# WiFi-Bee_v10.net
KiCad netlist of a schematic drawn in EAGLE
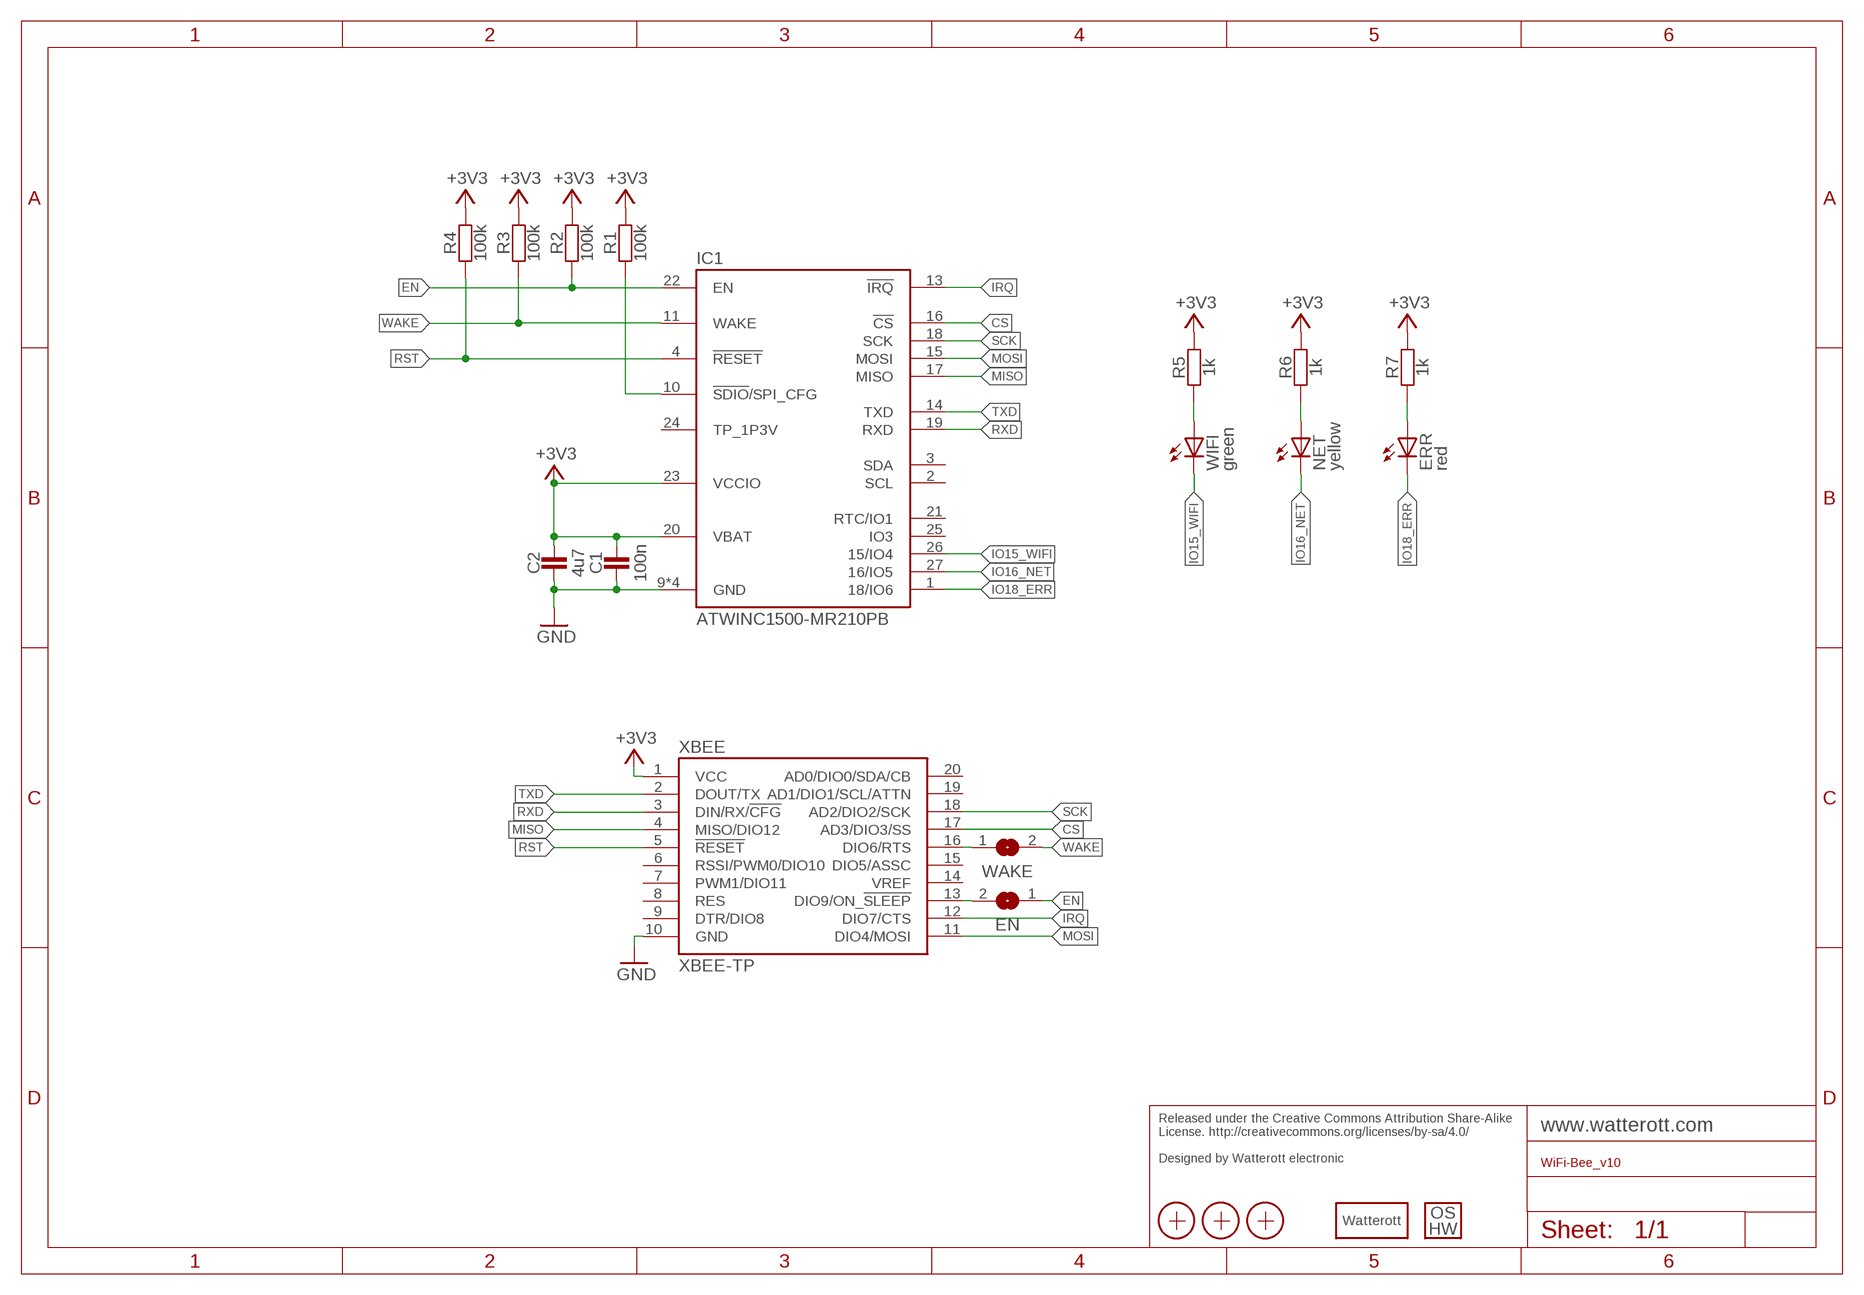
[diagram p0: schematic, sheet 1]

(export (version "E")
  (design (tool "Eeschema 10.0.6"))
  (components
    (comp (ref "C1")
      (value "100n")
      (footprint "eagle-import:C0402")
      (libsource (lib "eagle-import") (part "CAPACITOR-0402"))
    )
    (comp (ref "C2")
      (value "4u7")
      (footprint "eagle-import:C0402")
      (libsource (lib "eagle-import") (part "CAPACITOR-0402"))
    )
    (comp (ref "EN")
      (value "JUMPER2-0402")
      (footprint "eagle-import:JUMPER2-0402")
      (libsource (lib "eagle-import") (part "JUMPER2-0402"))
    )
    (comp (ref "ERR")
      (value "red")
      (footprint "eagle-import:C0603")
      (libsource (lib "eagle-import") (part "LED-0603"))
    )
    (comp (ref "IC1")
      (value "ATWINC1500-MR210PB")
      (footprint "eagle-import:ATWINC1500-MX210")
      (libsource (lib "eagle-import") (part "ATWINC1500-MR210PB"))
    )
    (comp (ref "LOGO3")
      (value "LOGO_SPARK-2")
      (footprint "eagle-import:SPARK_2MM")
      (libsource (lib "eagle-import") (part "LOGO_SPARK-2"))
    )
    (comp (ref "LOGO4")
      (value "LOGO_OSHW-2")
      (footprint "eagle-import:OSHW_2MM")
      (libsource (lib "eagle-import") (part "LOGO_OSHW-2"))
    )
    (comp (ref "NET")
      (value "yellow")
      (footprint "eagle-import:C0603")
      (libsource (lib "eagle-import") (part "LED-0603"))
    )
    (comp (ref "R1")
      (value "100k")
      (footprint "eagle-import:C0402")
      (libsource (lib "eagle-import") (part "RESISTOR-0402"))
    )
    (comp (ref "R2")
      (value "100k")
      (footprint "eagle-import:C0402")
      (libsource (lib "eagle-import") (part "RESISTOR-0402"))
    )
    (comp (ref "R3")
      (value "100k")
      (footprint "eagle-import:C0402")
      (libsource (lib "eagle-import") (part "RESISTOR-0402"))
    )
    (comp (ref "R4")
      (value "100k")
      (footprint "eagle-import:C0402")
      (libsource (lib "eagle-import") (part "RESISTOR-0402"))
    )
    (comp (ref "R5")
      (value "1k")
      (footprint "eagle-import:C0402")
      (libsource (lib "eagle-import") (part "RESISTOR-0402"))
    )
    (comp (ref "R6")
      (value "1k")
      (footprint "eagle-import:C0402")
      (libsource (lib "eagle-import") (part "RESISTOR-0402"))
    )
    (comp (ref "R7")
      (value "1k")
      (footprint "eagle-import:C0402")
      (libsource (lib "eagle-import") (part "RESISTOR-0402"))
    )
    (comp (ref "WAKE")
      (value "JUMPER2-0402")
      (footprint "eagle-import:JUMPER2-0402")
      (libsource (lib "eagle-import") (part "JUMPER2-0402"))
    )
    (comp (ref "WIFI")
      (value "green")
      (footprint "eagle-import:C0603")
      (libsource (lib "eagle-import") (part "LED-0603"))
    )
    (comp (ref "X1")
      (value "PASSER-07")
      (footprint "eagle-import:PASSER_07MM")
      (libsource (lib "eagle-import") (part "PASSER-07"))
    )
    (comp (ref "X2")
      (value "PASSER-07")
      (footprint "eagle-import:PASSER_07MM")
      (libsource (lib "eagle-import") (part "PASSER-07"))
    )
    (comp (ref "X3")
      (value "PASSER-07")
      (footprint "eagle-import:PASSER_07MM")
      (libsource (lib "eagle-import") (part "PASSER-07"))
    )
    (comp (ref "XBEE")
      (value "XBEE-TP")
      (footprint "eagle-import:XBEE_TP")
      (libsource (lib "eagle-import") (part "XBEE-TP"))
    )
  )
  (nets
    (net (code "1") (name "+3V3") (class "Default")
      (node (ref "C1") (pin "2") (pinfunction "2_2") (pintype "passive"))
      (node (ref "C2") (pin "2") (pinfunction "2_2") (pintype "passive"))
      (node (ref "IC1") (pin "20") (pinfunction "VBAT_20") (pintype "power_in"))
      (node (ref "IC1") (pin "23") (pinfunction "VCCIO_23") (pintype "power_in"))
      (node (ref "R1") (pin "2") (pinfunction "2_2") (pintype "passive"))
      (node (ref "R2") (pin "2") (pinfunction "2_2") (pintype "passive"))
      (node (ref "R3") (pin "2") (pinfunction "2_2") (pintype "passive"))
      (node (ref "R4") (pin "2") (pinfunction "2_2") (pintype "passive"))
      (node (ref "R5") (pin "2") (pinfunction "2_2") (pintype "passive"))
      (node (ref "R6") (pin "2") (pinfunction "2_2") (pintype "passive"))
      (node (ref "R7") (pin "2") (pinfunction "2_2") (pintype "passive"))
      (node (ref "XBEE") (pin "1") (pinfunction "VCC_1") (pintype "power_in"))
    )
    (net (code "2") (name "CS") (class "Default")
      (node (ref "IC1") (pin "16") (pinfunction "~{CS}_16") (pintype "input"))
      (node (ref "XBEE") (pin "17") (pinfunction "AD3/DIO3/SS_17") (pintype "bidirectional"))
    )
    (net (code "3") (name "EN") (class "Default")
      (node (ref "EN") (pin "1") (pinfunction "1_1") (pintype "passive"))
      (node (ref "IC1") (pin "22") (pinfunction "EN_22") (pintype "input"))
      (node (ref "R2") (pin "1") (pinfunction "1_1") (pintype "passive"))
    )
    (net (code "4") (name "GND") (class "Default")
      (node (ref "C1") (pin "1") (pinfunction "1_1") (pintype "passive"))
      (node (ref "C2") (pin "1") (pinfunction "1_1") (pintype "passive"))
      (node (ref "IC1") (pin "12") (pinfunction "GND_12") (pintype "power_in"))
      (node (ref "IC1") (pin "28") (pinfunction "GND_28") (pintype "power_in"))
      (node (ref "IC1") (pin "9") (pinfunction "GND_9") (pintype "power_in"))
      (node (ref "IC1") (pin "GND") (pinfunction "GND_GND") (pintype "power_in"))
      (node (ref "XBEE") (pin "10") (pinfunction "GND_10") (pintype "power_in"))
    )
    (net (code "5") (name "IO15_WIFI") (class "Default")
      (node (ref "IC1") (pin "26") (pinfunction "15/IO4_26") (pintype "bidirectional"))
      (node (ref "WIFI") (pin "C") (pinfunction "C_C") (pintype "passive"))
    )
    (net (code "6") (name "IO16_NET") (class "Default")
      (node (ref "IC1") (pin "27") (pinfunction "16/IO5_27") (pintype "bidirectional"))
      (node (ref "NET") (pin "C") (pinfunction "C_C") (pintype "passive"))
    )
    (net (code "7") (name "IO18_ERR") (class "Default")
      (node (ref "ERR") (pin "C") (pinfunction "C_C") (pintype "passive"))
      (node (ref "IC1") (pin "1") (pinfunction "18/IO6_1") (pintype "bidirectional"))
    )
    (net (code "8") (name "IRQ") (class "Default")
      (node (ref "IC1") (pin "13") (pinfunction "~{IRQ}_13") (pintype "output"))
      (node (ref "XBEE") (pin "12") (pinfunction "DIO7/CTS_12") (pintype "bidirectional"))
    )
    (net (code "9") (name "MISO") (class "Default")
      (node (ref "IC1") (pin "17") (pinfunction "MISO_17") (pintype "output"))
      (node (ref "XBEE") (pin "4") (pinfunction "MISO/DIO12_4") (pintype "bidirectional"))
    )
    (net (code "10") (name "MOSI") (class "Default")
      (node (ref "IC1") (pin "15") (pinfunction "MOSI_15") (pintype "input"))
      (node (ref "XBEE") (pin "11") (pinfunction "DIO4/MOSI_11") (pintype "bidirectional"))
    )
    (net (code "11") (name "Net-(ERR-PadA)") (class "Default")
      (node (ref "ERR") (pin "A") (pinfunction "A_A") (pintype "passive"))
      (node (ref "R7") (pin "1") (pinfunction "1_1") (pintype "passive"))
    )
    (net (code "12") (name "Net-(IC1-~{SDIO}{slash}SPI_CFG)") (class "Default")
      (node (ref "IC1") (pin "10") (pinfunction "~{SDIO}/SPI_CFG_10") (pintype "input"))
      (node (ref "R1") (pin "1") (pinfunction "1_1") (pintype "passive"))
    )
    (net (code "13") (name "Net-(NET-PadA)") (class "Default")
      (node (ref "NET") (pin "A") (pinfunction "A_A") (pintype "passive"))
      (node (ref "R6") (pin "1") (pinfunction "1_1") (pintype "passive"))
    )
    (net (code "14") (name "Net-(R5-Pad1)") (class "Default")
      (node (ref "R5") (pin "1") (pinfunction "1_1") (pintype "passive"))
      (node (ref "WIFI") (pin "A") (pinfunction "A_A") (pintype "passive"))
    )
    (net (code "15") (name "Net-(XBEE-DIO6{slash}RTS)") (class "Default")
      (node (ref "WAKE") (pin "1") (pinfunction "1_1") (pintype "passive"))
      (node (ref "XBEE") (pin "16") (pinfunction "DIO6/RTS_16") (pintype "bidirectional"))
    )
    (net (code "16") (name "Net-(XBEE-DIO9{slash}ON_~{SLEEP})") (class "Default")
      (node (ref "EN") (pin "2") (pinfunction "2_2") (pintype "passive"))
      (node (ref "XBEE") (pin "13") (pinfunction "DIO9/ON_~{SLEEP}_13") (pintype "bidirectional"))
    )
    (net (code "17") (name "RST") (class "Default")
      (node (ref "IC1") (pin "4") (pinfunction "~{RESET}_4") (pintype "input"))
      (node (ref "R4") (pin "1") (pinfunction "1_1") (pintype "passive"))
      (node (ref "XBEE") (pin "5") (pinfunction "~{RESET}_5") (pintype "bidirectional"))
    )
    (net (code "18") (name "RXD") (class "Default")
      (node (ref "IC1") (pin "19") (pinfunction "RXD_19") (pintype "input"))
      (node (ref "XBEE") (pin "3") (pinfunction "DIN/RX/~{CFG}_3") (pintype "bidirectional"))
    )
    (net (code "19") (name "SCK") (class "Default")
      (node (ref "IC1") (pin "18") (pinfunction "SCK_18") (pintype "input"))
      (node (ref "XBEE") (pin "18") (pinfunction "AD2/DIO2/SCK_18") (pintype "bidirectional"))
    )
    (net (code "20") (name "TXD") (class "Default")
      (node (ref "IC1") (pin "14") (pinfunction "TXD_14") (pintype "output"))
      (node (ref "XBEE") (pin "2") (pinfunction "DOUT/TX_2") (pintype "bidirectional"))
    )
    (net (code "21") (name "WAKE") (class "Default")
      (node (ref "IC1") (pin "11") (pinfunction "WAKE_11") (pintype "input"))
      (node (ref "R3") (pin "1") (pinfunction "1_1") (pintype "passive"))
      (node (ref "WAKE") (pin "2") (pinfunction "2_2") (pintype "passive"))
    )
    (net (code "22") (name "unconnected-(IC1-IO3-Pad25)") (class "Default")
      (node (ref "IC1") (pin "25") (pinfunction "IO3_25") (pintype "bidirectional"))
    )
    (net (code "23") (name "unconnected-(IC1-RTC{slash}IO1-Pad21)") (class "Default")
      (node (ref "IC1") (pin "21") (pinfunction "RTC/IO1_21") (pintype "bidirectional"))
    )
    (net (code "24") (name "unconnected-(IC1-SCL-Pad2)") (class "Default")
      (node (ref "IC1") (pin "2") (pinfunction "SCL_2") (pintype "bidirectional"))
    )
    (net (code "25") (name "unconnected-(IC1-SDA-Pad3)") (class "Default")
      (node (ref "IC1") (pin "3") (pinfunction "SDA_3") (pintype "bidirectional"))
    )
    (net (code "26") (name "unconnected-(IC1-TP_1P3V-Pad24)") (class "Default")
      (node (ref "IC1") (pin "24") (pinfunction "TP_1P3V_24") (pintype "bidirectional"))
    )
    (net (code "27") (name "unconnected-(XBEE-AD0{slash}DIO0{slash}SDA{slash}CB-Pad20)") (class "Default")
      (node (ref "XBEE") (pin "20") (pinfunction "AD0/DIO0/SDA/CB_20") (pintype "bidirectional"))
    )
    (net (code "28") (name "unconnected-(XBEE-AD1{slash}DIO1{slash}SCL{slash}ATTN-Pad19)") (class "Default")
      (node (ref "XBEE") (pin "19") (pinfunction "AD1/DIO1/SCL/ATTN_19") (pintype "bidirectional"))
    )
    (net (code "29") (name "unconnected-(XBEE-DIO5{slash}ASSC-Pad15)") (class "Default")
      (node (ref "XBEE") (pin "15") (pinfunction "DIO5/ASSC_15") (pintype "bidirectional"))
    )
    (net (code "30") (name "unconnected-(XBEE-DTR{slash}DIO8-Pad9)") (class "Default")
      (node (ref "XBEE") (pin "9") (pinfunction "DTR/DIO8_9") (pintype "bidirectional"))
    )
    (net (code "31") (name "unconnected-(XBEE-PWM1{slash}DIO11-Pad7)") (class "Default")
      (node (ref "XBEE") (pin "7") (pinfunction "PWM1/DIO11_7") (pintype "bidirectional"))
    )
    (net (code "32") (name "unconnected-(XBEE-RES-Pad8)") (class "Default")
      (node (ref "XBEE") (pin "8") (pinfunction "RES_8") (pintype "bidirectional"))
    )
    (net (code "33") (name "unconnected-(XBEE-RSSI{slash}PWM0{slash}DIO10-Pad6)") (class "Default")
      (node (ref "XBEE") (pin "6") (pinfunction "RSSI/PWM0/DIO10_6") (pintype "bidirectional"))
    )
    (net (code "34") (name "unconnected-(XBEE-VREF-Pad14)") (class "Default")
      (node (ref "XBEE") (pin "14") (pinfunction "VREF_14") (pintype "bidirectional"))
    )
  )
)
